# untitled.net
KiCad netlist of a schematic drawn in EAGLE
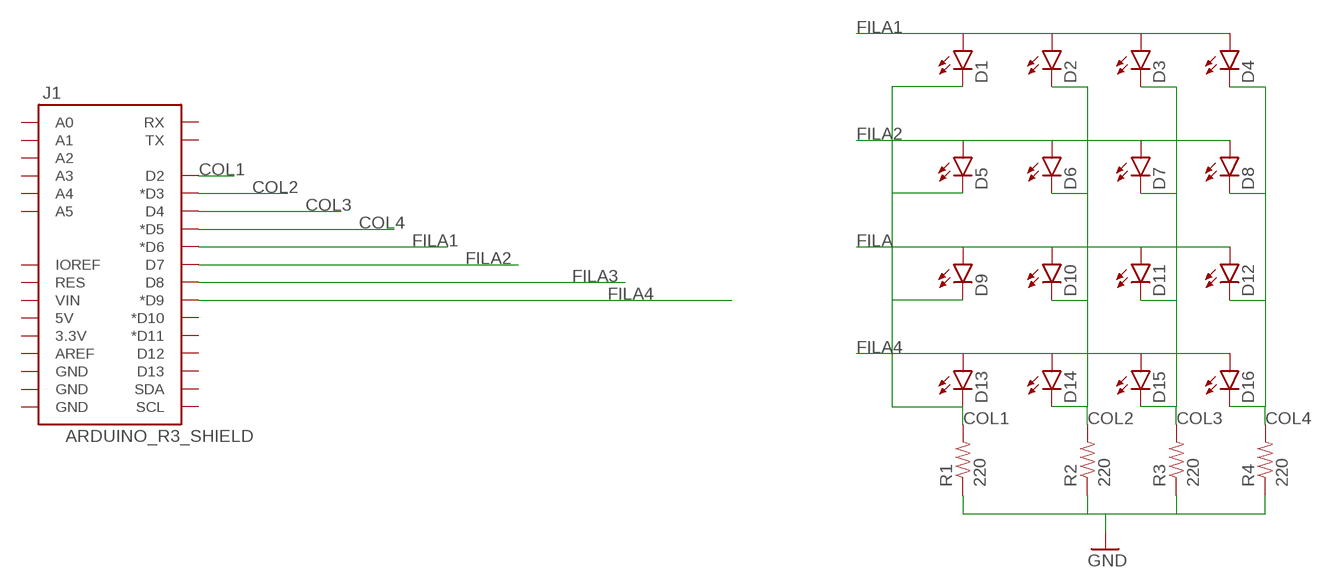
[diagram p0: schematic, sheet 1]

(export (version "E")
  (design (tool "Eeschema 10.0.6"))
  (components
    (comp (ref "D1")
      (value "LED5MM")
      (footprint "eagle-import:LED5MM")
      (libsource (lib "eagle-import") (part "LED5MM"))
    )
    (comp (ref "D2")
      (value "LED5MM")
      (footprint "eagle-import:LED5MM")
      (libsource (lib "eagle-import") (part "LED5MM"))
    )
    (comp (ref "D3")
      (value "LED5MM")
      (footprint "eagle-import:LED5MM")
      (libsource (lib "eagle-import") (part "LED5MM"))
    )
    (comp (ref "D4")
      (value "LED5MM")
      (footprint "eagle-import:LED5MM")
      (libsource (lib "eagle-import") (part "LED5MM"))
    )
    (comp (ref "D5")
      (value "LED5MM")
      (footprint "eagle-import:LED5MM")
      (libsource (lib "eagle-import") (part "LED5MM"))
    )
    (comp (ref "D6")
      (value "LED5MM")
      (footprint "eagle-import:LED5MM")
      (libsource (lib "eagle-import") (part "LED5MM"))
    )
    (comp (ref "D7")
      (value "LED5MM")
      (footprint "eagle-import:LED5MM")
      (libsource (lib "eagle-import") (part "LED5MM"))
    )
    (comp (ref "D8")
      (value "LED5MM")
      (footprint "eagle-import:LED5MM")
      (libsource (lib "eagle-import") (part "LED5MM"))
    )
    (comp (ref "D9")
      (value "LED5MM")
      (footprint "eagle-import:LED5MM")
      (libsource (lib "eagle-import") (part "LED5MM"))
    )
    (comp (ref "D10")
      (value "LED5MM")
      (footprint "eagle-import:LED5MM")
      (libsource (lib "eagle-import") (part "LED5MM"))
    )
    (comp (ref "D11")
      (value "LED5MM")
      (footprint "eagle-import:LED5MM")
      (libsource (lib "eagle-import") (part "LED5MM"))
    )
    (comp (ref "D12")
      (value "LED5MM")
      (footprint "eagle-import:LED5MM")
      (libsource (lib "eagle-import") (part "LED5MM"))
    )
    (comp (ref "D13")
      (value "LED5MM")
      (footprint "eagle-import:LED5MM")
      (libsource (lib "eagle-import") (part "LED5MM"))
    )
    (comp (ref "D14")
      (value "LED5MM")
      (footprint "eagle-import:LED5MM")
      (libsource (lib "eagle-import") (part "LED5MM"))
    )
    (comp (ref "D15")
      (value "LED5MM")
      (footprint "eagle-import:LED5MM")
      (libsource (lib "eagle-import") (part "LED5MM"))
    )
    (comp (ref "D16")
      (value "LED5MM")
      (footprint "eagle-import:LED5MM")
      (libsource (lib "eagle-import") (part "LED5MM"))
    )
    (comp (ref "J1")
      (value "ARDUINO_R3_SHIELD")
      (footprint "eagle-import:UNO_R3_SHIELD")
      (libsource (lib "eagle-import") (part "ARDUINO_R3_SHIELD"))
    )
    (comp (ref "R1")
      (value "220")
      (footprint "eagle-import:AXIAL-0.4")
      (libsource (lib "eagle-import") (part "RESISTORPTH-1/4W"))
    )
    (comp (ref "R2")
      (value "220")
      (footprint "eagle-import:AXIAL-0.4")
      (libsource (lib "eagle-import") (part "RESISTORPTH-1/4W"))
    )
    (comp (ref "R3")
      (value "220")
      (footprint "eagle-import:AXIAL-0.4")
      (libsource (lib "eagle-import") (part "RESISTORPTH-1/4W"))
    )
    (comp (ref "R4")
      (value "220")
      (footprint "eagle-import:AXIAL-0.4")
      (libsource (lib "eagle-import") (part "RESISTORPTH-1/4W"))
    )
  )
  (nets
    (net (code "1") (name "/COL1") (class "Default")
      (node (ref "D1") (pin "K") (pinfunction "C_K") (pintype "passive"))
      (node (ref "D13") (pin "K") (pinfunction "C_K") (pintype "passive"))
      (node (ref "D5") (pin "K") (pinfunction "C_K") (pintype "passive"))
      (node (ref "D9") (pin "K") (pinfunction "C_K") (pintype "passive"))
      (node (ref "J1") (pin "D2") (pinfunction "D2_D2") (pintype "bidirectional"))
      (node (ref "R1") (pin "P$2") (pinfunction "2_P$2") (pintype "passive"))
    )
    (net (code "2") (name "/COL2") (class "Default")
      (node (ref "D10") (pin "K") (pinfunction "C_K") (pintype "passive"))
      (node (ref "D14") (pin "K") (pinfunction "C_K") (pintype "passive"))
      (node (ref "D2") (pin "K") (pinfunction "C_K") (pintype "passive"))
      (node (ref "D6") (pin "K") (pinfunction "C_K") (pintype "passive"))
      (node (ref "J1") (pin "D3") (pinfunction "*D3_D3") (pintype "bidirectional"))
      (node (ref "R2") (pin "P$2") (pinfunction "2_P$2") (pintype "passive"))
    )
    (net (code "3") (name "/COL3") (class "Default")
      (node (ref "D11") (pin "K") (pinfunction "C_K") (pintype "passive"))
      (node (ref "D15") (pin "K") (pinfunction "C_K") (pintype "passive"))
      (node (ref "D3") (pin "K") (pinfunction "C_K") (pintype "passive"))
      (node (ref "D7") (pin "K") (pinfunction "C_K") (pintype "passive"))
      (node (ref "J1") (pin "D4") (pinfunction "D4_D4") (pintype "bidirectional"))
      (node (ref "R3") (pin "P$2") (pinfunction "2_P$2") (pintype "passive"))
    )
    (net (code "4") (name "/COL4") (class "Default")
      (node (ref "D12") (pin "K") (pinfunction "C_K") (pintype "passive"))
      (node (ref "D16") (pin "K") (pinfunction "C_K") (pintype "passive"))
      (node (ref "D4") (pin "K") (pinfunction "C_K") (pintype "passive"))
      (node (ref "D8") (pin "K") (pinfunction "C_K") (pintype "passive"))
      (node (ref "J1") (pin "D5") (pinfunction "*D5_D5") (pintype "bidirectional"))
      (node (ref "R4") (pin "P$2") (pinfunction "2_P$2") (pintype "passive"))
    )
    (net (code "5") (name "/FILA") (class "Default")
      (node (ref "D12") (pin "A") (pinfunction "A_A") (pintype "passive"))
    )
    (net (code "6") (name "/FILA1") (class "Default")
      (node (ref "D4") (pin "A") (pinfunction "A_A") (pintype "passive"))
      (node (ref "J1") (pin "D6") (pinfunction "*D6_D6") (pintype "bidirectional"))
    )
    (net (code "7") (name "/FILA2") (class "Default")
      (node (ref "D8") (pin "A") (pinfunction "A_A") (pintype "passive"))
      (node (ref "J1") (pin "D7") (pinfunction "D7_D7") (pintype "bidirectional"))
    )
    (net (code "8") (name "/FILA3") (class "Default")
      (node (ref "J1") (pin "D8") (pinfunction "D8_D8") (pintype "bidirectional"))
    )
    (net (code "9") (name "/FILA4") (class "Default")
      (node (ref "D16") (pin "A") (pinfunction "A_A") (pintype "passive"))
      (node (ref "J1") (pin "D9") (pinfunction "*D9_D9") (pintype "bidirectional"))
    )
    (net (code "10") (name "GND") (class "Default")
      (node (ref "R1") (pin "P$1") (pinfunction "1_P$1") (pintype "passive"))
      (node (ref "R2") (pin "P$1") (pinfunction "1_P$1") (pintype "passive"))
      (node (ref "R3") (pin "P$1") (pinfunction "1_P$1") (pintype "passive"))
      (node (ref "R4") (pin "P$1") (pinfunction "1_P$1") (pintype "passive"))
    )
    (net (code "11") (name "unconnected-(D1-PadA)") (class "Default")
      (node (ref "D1") (pin "A") (pinfunction "A_A") (pintype "passive"))
    )
    (net (code "12") (name "unconnected-(D2-PadA)") (class "Default")
      (node (ref "D2") (pin "A") (pinfunction "A_A") (pintype "passive"))
    )
    (net (code "13") (name "unconnected-(D3-PadA)") (class "Default")
      (node (ref "D3") (pin "A") (pinfunction "A_A") (pintype "passive"))
    )
    (net (code "14") (name "unconnected-(D5-PadA)") (class "Default")
      (node (ref "D5") (pin "A") (pinfunction "A_A") (pintype "passive"))
    )
    (net (code "15") (name "unconnected-(D6-PadA)") (class "Default")
      (node (ref "D6") (pin "A") (pinfunction "A_A") (pintype "passive"))
    )
    (net (code "16") (name "unconnected-(D7-PadA)") (class "Default")
      (node (ref "D7") (pin "A") (pinfunction "A_A") (pintype "passive"))
    )
    (net (code "17") (name "unconnected-(D9-PadA)") (class "Default")
      (node (ref "D9") (pin "A") (pinfunction "A_A") (pintype "passive"))
    )
    (net (code "18") (name "unconnected-(D10-PadA)") (class "Default")
      (node (ref "D10") (pin "A") (pinfunction "A_A") (pintype "passive"))
    )
    (net (code "19") (name "unconnected-(D11-PadA)") (class "Default")
      (node (ref "D11") (pin "A") (pinfunction "A_A") (pintype "passive"))
    )
    (net (code "20") (name "unconnected-(D13-PadA)") (class "Default")
      (node (ref "D13") (pin "A") (pinfunction "A_A") (pintype "passive"))
    )
    (net (code "21") (name "unconnected-(D14-PadA)") (class "Default")
      (node (ref "D14") (pin "A") (pinfunction "A_A") (pintype "passive"))
    )
    (net (code "22") (name "unconnected-(D15-PadA)") (class "Default")
      (node (ref "D15") (pin "A") (pinfunction "A_A") (pintype "passive"))
    )
    (net (code "23") (name "unconnected-(J1-*D10-PadD10)") (class "Default")
      (node (ref "J1") (pin "D10") (pinfunction "*D10_D10") (pintype "bidirectional"))
    )
    (net (code "24") (name "unconnected-(J1-*D11-PadD11)") (class "Default")
      (node (ref "J1") (pin "D11") (pinfunction "*D11_D11") (pintype "bidirectional"))
    )
    (net (code "25") (name "unconnected-(J1-GND-PadGND@0)") (class "Default")
      (node (ref "J1") (pin "GND@0") (pinfunction "GND_GND@0") (pintype "bidirectional"))
    )
    (net (code "26") (name "unconnected-(J1-GND-PadGND@1)") (class "Default")
      (node (ref "J1") (pin "GND@1") (pinfunction "GND_GND@1") (pintype "bidirectional"))
    )
    (net (code "27") (name "unconnected-(J1-GND-PadGND@2)") (class "Default")
      (node (ref "J1") (pin "GND@2") (pinfunction "GND_GND@2") (pintype "bidirectional"))
    )
    (net (code "28") (name "unconnected-(J1-Pad3.3V)") (class "Default")
      (node (ref "J1") (pin "3.3V") (pinfunction "3.3V_3.3V") (pintype "bidirectional"))
    )
    (net (code "29") (name "unconnected-(J1-Pad5V)") (class "Default")
      (node (ref "J1") (pin "5V") (pinfunction "5V_5V") (pintype "bidirectional"))
    )
    (net (code "30") (name "unconnected-(J1-PadA0)") (class "Default")
      (node (ref "J1") (pin "A0") (pinfunction "A0_A0") (pintype "bidirectional"))
    )
    (net (code "31") (name "unconnected-(J1-PadA1)") (class "Default")
      (node (ref "J1") (pin "A1") (pinfunction "A1_A1") (pintype "bidirectional"))
    )
    (net (code "32") (name "unconnected-(J1-PadA2)") (class "Default")
      (node (ref "J1") (pin "A2") (pinfunction "A2_A2") (pintype "bidirectional"))
    )
    (net (code "33") (name "unconnected-(J1-PadA3)") (class "Default")
      (node (ref "J1") (pin "A3") (pinfunction "A3_A3") (pintype "bidirectional"))
    )
    (net (code "34") (name "unconnected-(J1-PadA4)") (class "Default")
      (node (ref "J1") (pin "A4") (pinfunction "A4_A4") (pintype "bidirectional"))
    )
    (net (code "35") (name "unconnected-(J1-PadA5)") (class "Default")
      (node (ref "J1") (pin "A5") (pinfunction "A5_A5") (pintype "bidirectional"))
    )
    (net (code "36") (name "unconnected-(J1-PadAREF)") (class "Default")
      (node (ref "J1") (pin "AREF") (pinfunction "AREF_AREF") (pintype "bidirectional"))
    )
    (net (code "37") (name "unconnected-(J1-PadD12)") (class "Default")
      (node (ref "J1") (pin "D12") (pinfunction "D12_D12") (pintype "bidirectional"))
    )
    (net (code "38") (name "unconnected-(J1-PadD13)") (class "Default")
      (node (ref "J1") (pin "D13") (pinfunction "D13_D13") (pintype "bidirectional"))
    )
    (net (code "39") (name "unconnected-(J1-PadIOREF)") (class "Default")
      (node (ref "J1") (pin "IOREF") (pinfunction "IOREF_IOREF") (pintype "bidirectional"))
    )
    (net (code "40") (name "unconnected-(J1-PadRES)") (class "Default")
      (node (ref "J1") (pin "RES") (pinfunction "RES_RES") (pintype "bidirectional"))
    )
    (net (code "41") (name "unconnected-(J1-PadRX)") (class "Default")
      (node (ref "J1") (pin "RX") (pinfunction "RX_RX") (pintype "bidirectional"))
    )
    (net (code "42") (name "unconnected-(J1-PadSCL)") (class "Default")
      (node (ref "J1") (pin "SCL") (pinfunction "SCL_SCL") (pintype "bidirectional"))
    )
    (net (code "43") (name "unconnected-(J1-PadSDA)") (class "Default")
      (node (ref "J1") (pin "SDA") (pinfunction "SDA_SDA") (pintype "bidirectional"))
    )
    (net (code "44") (name "unconnected-(J1-PadTX)") (class "Default")
      (node (ref "J1") (pin "TX") (pinfunction "TX_TX") (pintype "bidirectional"))
    )
    (net (code "45") (name "unconnected-(J1-PadVIN)") (class "Default")
      (node (ref "J1") (pin "VIN") (pinfunction "VIN_VIN") (pintype "bidirectional"))
    )
  )
)
